# nRF24L01.net
KiCad netlist of a schematic drawn in Altium Designer
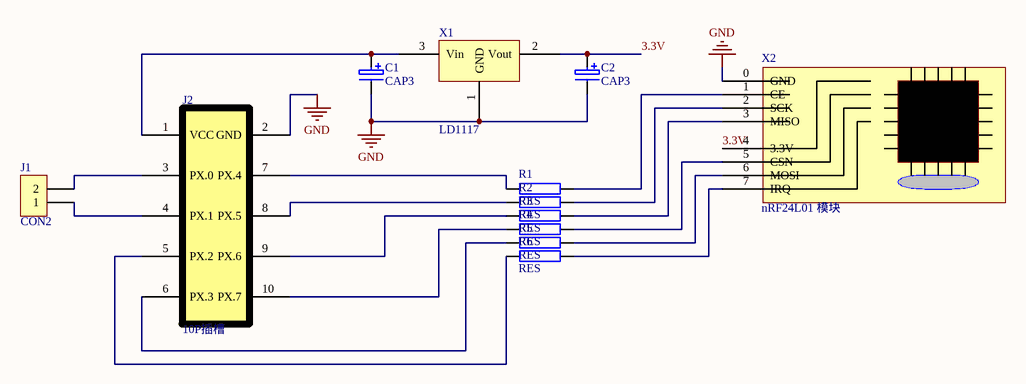
[diagram p0: nRF24L01 无线收发.SchDoc]

(export (version "E")
  (design (tool "Eeschema 10.0.6"))
  (components
    (comp (ref "C1") (value "CAP3") (footprint "CAO1") (libsource (lib "C电容") (part "CAP3")))
    (comp (ref "C2") (value "CAP3") (footprint "CAO1") (libsource (lib "C电容") (part "CAP3")))
    (comp (ref "J1")
      (value "CON2")
      (footprint "sip-2")
      (description "Connector")
      (libsource (lib "接口") (part "CON2"))
    )
    (comp (ref "J2") (value "10P插槽") (footprint "10P插槽") (libsource (lib "刘杨_元件库") (part "10P插槽")))
    (comp (ref "R1") (value "RES") (footprint "AXIAL0.3") (libsource (lib "R电阻") (part "RES")))
    (comp (ref "R2") (value "RES") (footprint "AXIAL0.3") (libsource (lib "R电阻") (part "RES")))
    (comp (ref "R3") (value "RES") (footprint "AXIAL0.3") (libsource (lib "R电阻") (part "RES")))
    (comp (ref "R4") (value "RES") (footprint "AXIAL0.3") (libsource (lib "R电阻") (part "RES")))
    (comp (ref "R5") (value "RES") (footprint "AXIAL0.3") (libsource (lib "R电阻") (part "RES")))
    (comp (ref "R6") (value "RES") (footprint "AXIAL0.3") (libsource (lib "R电阻") (part "RES")))
    (comp (ref "X1") (value "LD1117") (footprint "SOT-223") (libsource (lib "刘杨_元件库") (part "LD1117")))
    (comp (ref "X2")
      (value "nRF24L01 模块")
      (footprint "nRF24L01模块")
      (libsource (lib "刘杨_元件库") (part "nRF24L01 模块"))
    )
  )
  (nets
    (net (code "1") (name "/3.3V") (class "Default")
      (node (ref "C2") (pin "1") (pintype "passive"))
      (node (ref "X1") (pin "2") (pinfunction "Vout_2") (pintype "passive"))
      (node (ref "X2") (pin "4") (pinfunction "3.3V_4") (pintype "passive"))
    )
    (net (code "2") (name "GND") (class "Default")
      (node (ref "C1") (pin "2") (pintype "passive"))
      (node (ref "C2") (pin "2") (pintype "passive"))
      (node (ref "J2") (pin "2") (pinfunction "GND_2") (pintype "passive"))
      (node (ref "X1") (pin "1") (pinfunction "GND_1") (pintype "passive"))
      (node (ref "X2") (pin "0") (pinfunction "GND_0") (pintype "passive"))
    )
    (net (code "3") (name "Net-(J2-PX.0)") (class "Default")
      (node (ref "J1") (pin "2") (pinfunction "2_2") (pintype "passive"))
      (node (ref "J2") (pin "3") (pinfunction "PX.0_3") (pintype "passive"))
    )
    (net (code "4") (name "Net-(J2-PX.1)") (class "Default")
      (node (ref "J1") (pin "1") (pinfunction "1_1") (pintype "passive"))
      (node (ref "J2") (pin "4") (pinfunction "PX.1_4") (pintype "passive"))
    )
    (net (code "5") (name "Net-(J2-PX.2)") (class "Default")
      (node (ref "J2") (pin "5") (pinfunction "PX.2_5") (pintype "passive"))
      (node (ref "R6") (pin "1") (pinfunction "1_1") (pintype "passive"))
    )
    (net (code "6") (name "Net-(J2-PX.3)") (class "Default")
      (node (ref "J2") (pin "6") (pinfunction "PX.3_6") (pintype "passive"))
      (node (ref "R5") (pin "1") (pinfunction "1_1") (pintype "passive"))
    )
    (net (code "7") (name "Net-(J2-PX.4)") (class "Default")
      (node (ref "J2") (pin "7") (pinfunction "PX.4_7") (pintype "passive"))
      (node (ref "R1") (pin "1") (pinfunction "1_1") (pintype "passive"))
    )
    (net (code "8") (name "Net-(J2-PX.5)") (class "Default")
      (node (ref "J2") (pin "8") (pinfunction "PX.5_8") (pintype "passive"))
      (node (ref "R2") (pin "1") (pinfunction "1_1") (pintype "passive"))
    )
    (net (code "9") (name "Net-(J2-PX.6)") (class "Default")
      (node (ref "J2") (pin "9") (pinfunction "PX.6_9") (pintype "passive"))
      (node (ref "R3") (pin "1") (pinfunction "1_1") (pintype "passive"))
    )
    (net (code "10") (name "Net-(J2-PX.7)") (class "Default")
      (node (ref "J2") (pin "10") (pinfunction "PX.7_10") (pintype "passive"))
      (node (ref "R4") (pin "1") (pinfunction "1_1") (pintype "passive"))
    )
    (net (code "11") (name "Net-(J2-VCC)") (class "Default")
      (node (ref "C1") (pin "1") (pintype "passive"))
      (node (ref "J2") (pin "1") (pinfunction "VCC_1") (pintype "passive"))
      (node (ref "X1") (pin "3") (pinfunction "Vin_3") (pintype "passive"))
    )
    (net (code "12") (name "Net-(X2-CE)") (class "Default")
      (node (ref "R1") (pin "2") (pinfunction "2_2") (pintype "passive"))
      (node (ref "X2") (pin "1") (pinfunction "CE_1") (pintype "passive"))
    )
    (net (code "13") (name "Net-(X2-CSN)") (class "Default")
      (node (ref "R4") (pin "2") (pinfunction "2_2") (pintype "passive"))
      (node (ref "X2") (pin "5") (pinfunction "CSN_5") (pintype "passive"))
    )
    (net (code "14") (name "Net-(X2-IRQ)") (class "Default")
      (node (ref "R6") (pin "2") (pinfunction "2_2") (pintype "passive"))
      (node (ref "X2") (pin "7") (pinfunction "IRQ_7") (pintype "passive"))
    )
    (net (code "15") (name "Net-(X2-MISO)") (class "Default")
      (node (ref "R3") (pin "2") (pinfunction "2_2") (pintype "passive"))
      (node (ref "X2") (pin "3") (pinfunction "MISO_3") (pintype "passive"))
    )
    (net (code "16") (name "Net-(X2-MOSI)") (class "Default")
      (node (ref "R5") (pin "2") (pinfunction "2_2") (pintype "passive"))
      (node (ref "X2") (pin "6") (pinfunction "MOSI_6") (pintype "passive"))
    )
    (net (code "17") (name "Net-(X2-SCK)") (class "Default")
      (node (ref "R2") (pin "2") (pinfunction "2_2") (pintype "passive"))
      (node (ref "X2") (pin "2") (pinfunction "SCK_2") (pintype "passive"))
    )
  )
)
